# 06_TOFs.net
KiCad netlist of a schematic drawn in Altium Designer
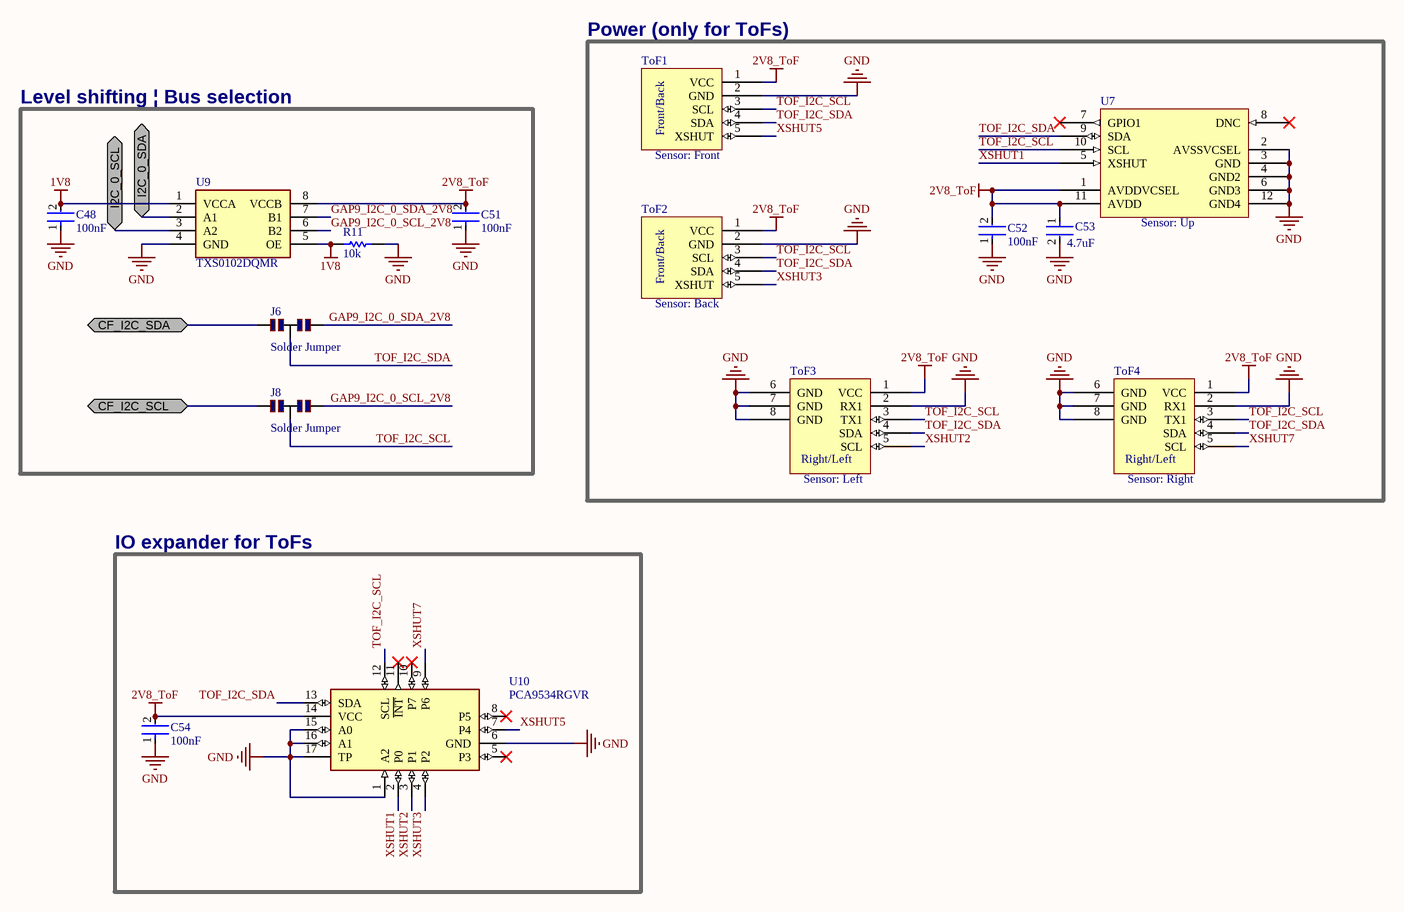
[diagram p0: 06_TOFs.SchDoc]

(export (version "E")
  (design (tool "Eeschema 10.0.6"))
  (components
    (comp (ref "C48")
      (value "100nF")
      (footprint "FP-C1005-050-0_05-MFG")
      (description "Multilayer Ceramic Capacitors 100nF ±10% 25V X5R SMD 0402")
      (fields (field (name "TOLERANCE") "10%") (field (name "VOLTAGE") "25V"))
      (libsource (lib "Altium Content Vault") (part "b4654b650e69147ec39a6b967a45e02"))
    )
    (comp (ref "C51")
      (value "100nF")
      (footprint "FP-C1005-050-0_05-MFG")
      (description "Multilayer Ceramic Capacitors 100nF ±10% 25V X5R SMD 0402")
      (fields (field (name "TOLERANCE") "10%") (field (name "VOLTAGE") "25V"))
      (libsource (lib "Altium Content Vault") (part "b4654b650e69147ec39a6b967a45e02"))
    )
    (comp (ref "C52")
      (value "100nF")
      (footprint "FP-C1005-050-0_05-MFG")
      (description "Multilayer Ceramic Capacitors 100nF ±10% 25V X5R SMD 0402")
      (fields (field (name "TOLERANCE") "10%") (field (name "VOLTAGE") "25V"))
      (libsource (lib "Altium Content Vault") (part "b4654b650e69147ec39a6b967a45e02"))
    )
    (comp (ref "C53")
      (value "4.7uF")
      (footprint "FP-C1005-050-0_15-MFG")
      (description "CAP CER 4.7UF 6.3V X5R 0402")
      (fields (field (name "VOLTAGE") "6.3V") (field (name "TOLERANCE") "10%"))
      (libsource (lib "Altium Content Vault") (part "02cd4be3c70576c341d710602a673aa"))
    )
    (comp (ref "C54")
      (value "100nF")
      (footprint "FP-C1005-050-0_05-MFG")
      (description "Multilayer Ceramic Capacitors 100nF ±10% 25V X5R SMD 0402")
      (fields (field (name "TOLERANCE") "10%") (field (name "VOLTAGE") "25V"))
      (libsource (lib "Altium Content Vault") (part "b4654b650e69147ec39a6b967a45e02"))
    )
    (comp (ref "J6")
      (value "Solder Jumper")
      (footprint "Jumper 3 pins")
      (description "Solder Jumper 3 Pads")
      (libsource (lib "gap9_deck") (part "CMP-00467-5"))
    )
    (comp (ref "J8")
      (value "Solder Jumper")
      (footprint "Jumper 3 pins")
      (description "Solder Jumper 3 Pads")
      (libsource (lib "gap9_deck") (part "CMP-00467-5"))
    )
    (comp (ref "R11")
      (value "10k")
      (footprint "RESC0603X28X15LL05T05")
      (fields (field (name "MANUFACTURER") "Vishay Dale") (field (name "PART NUMBER") "CRCW020110K0FNED"))
      (libsource (lib "Altium Content Vault") (part "RES"))
    )
    (comp (ref "ToF1")
      (value "~")
      (footprint "ToF_Front_Back")
      (description "ToF PCBs (DNM)")
      (libsource (lib "gap9_deck") (part "ToF_Front_Back"))
    )
    (comp (ref "ToF2")
      (value "~")
      (footprint "ToF_Front_Back")
      (description "ToF PCBs (DNM)")
      (libsource (lib "gap9_deck") (part "ToF_Front_Back"))
    )
    (comp (ref "ToF3")
      (value "~")
      (footprint "ToF_Right_Left")
      (libsource (lib "gap9_deck") (part "ToF_Right_Letf"))
    )
    (comp (ref "ToF4")
      (value "~")
      (footprint "ToF_Right_Left")
      (libsource (lib "gap9_deck") (part "ToF_Right_Letf"))
    )
    (comp (ref "U7")
      (value "VL53L1CXV0FY/1")
      (footprint "TOF")
      (fields (field (name "MANUFACTURER") "STMicroelectronics"))
      (libsource (lib "Pulp_Shield_wolf") (part "VL53L1X"))
    )
    (comp (ref "U9")
      (value "TXS0102DQMR")
      (footprint "SON40P120X180X40-8N")
      (description "Integrated Circuit")
      (fields (field (name "MOUSER PART NUMBER") "595-TXS0102DQMR"))
      (libsource (lib "*") (part "TXS0102DQMR"))
    )
    (comp (ref "U10")
      (value "PCA9534RGVR")
      (footprint "SamacSys:QFN65P400X400X100-17N-D")
      (description "Undefined or Miscellaneous")
      (fields (field (name "MOUSER PART NUMBER") "595-PCA9534RGVR"))
      (libsource (lib "*") (part "PCA9534RGVR"))
    )
  )
  (nets
    (net (code "1") (name "/CF_I2C_SCL") (class "Default")
      (node (ref "J8") (pin "1") (pinfunction "1_1") (pintype "passive"))
    )
    (net (code "2") (name "/CF_I2C_SDA") (class "Default")
      (node (ref "J6") (pin "1") (pinfunction "1_1") (pintype "passive"))
    )
    (net (code "3") (name "/GAP9_I2C_0_SCL_2V8") (class "Default")
      (node (ref "J8") (pin "3") (pinfunction "3_3") (pintype "passive"))
      (node (ref "U9") (pin "6") (pinfunction "B2_6") (pintype "passive"))
    )
    (net (code "4") (name "/GAP9_I2C_0_SDA_2V8") (class "Default")
      (node (ref "J6") (pin "3") (pinfunction "3_3") (pintype "passive"))
      (node (ref "U9") (pin "7") (pinfunction "B1_7") (pintype "passive"))
    )
    (net (code "5") (name "/I2C_0_SCL") (class "Default")
      (node (ref "U9") (pin "3") (pinfunction "A2_3") (pintype "passive"))
    )
    (net (code "6") (name "/I2C_0_SDA") (class "Default")
      (node (ref "U9") (pin "2") (pinfunction "A1_2") (pintype "passive"))
    )
    (net (code "7") (name "/TOF_I2C_SCL") (class "Default")
      (node (ref "J8") (pin "2") (pinfunction "2_2") (pintype "passive"))
      (node (ref "ToF1") (pin "3") (pinfunction "SCL_3") (pintype "bidirectional"))
      (node (ref "ToF2") (pin "3") (pinfunction "SCL_3") (pintype "bidirectional"))
      (node (ref "ToF3") (pin "3") (pinfunction "TX1_3") (pintype "bidirectional"))
      (node (ref "ToF4") (pin "3") (pinfunction "TX1_3") (pintype "bidirectional"))
      (node (ref "U10") (pin "12") (pinfunction "SCL_12") (pintype "bidirectional"))
      (node (ref "U7") (pin "10") (pinfunction "SCL_10") (pintype "input"))
    )
    (net (code "8") (name "/TOF_I2C_SDA") (class "Default")
      (node (ref "J6") (pin "2") (pinfunction "2_2") (pintype "passive"))
      (node (ref "ToF1") (pin "4") (pinfunction "SDA_4") (pintype "bidirectional"))
      (node (ref "ToF2") (pin "4") (pinfunction "SDA_4") (pintype "bidirectional"))
      (node (ref "ToF3") (pin "4") (pinfunction "SDA_4") (pintype "bidirectional"))
      (node (ref "ToF4") (pin "4") (pinfunction "SDA_4") (pintype "bidirectional"))
      (node (ref "U10") (pin "13") (pinfunction "SDA_13") (pintype "bidirectional"))
      (node (ref "U7") (pin "9") (pinfunction "SDA_9") (pintype "bidirectional"))
    )
    (net (code "9") (name "/XSHUT1") (class "Default")
      (node (ref "U10") (pin "2") (pinfunction "P0_2") (pintype "bidirectional"))
      (node (ref "U7") (pin "5") (pinfunction "XSHUT_5") (pintype "input"))
    )
    (net (code "10") (name "/XSHUT2") (class "Default")
      (node (ref "ToF3") (pin "5") (pinfunction "SCL_5") (pintype "bidirectional"))
      (node (ref "U10") (pin "3") (pinfunction "P1_3") (pintype "bidirectional"))
    )
    (net (code "11") (name "/XSHUT3") (class "Default")
      (node (ref "ToF2") (pin "5") (pinfunction "XSHUT_5") (pintype "bidirectional"))
      (node (ref "U10") (pin "4") (pinfunction "P2_4") (pintype "bidirectional"))
    )
    (net (code "12") (name "/XSHUT5") (class "Default")
      (node (ref "ToF1") (pin "5") (pinfunction "XSHUT_5") (pintype "bidirectional"))
      (node (ref "U10") (pin "7") (pinfunction "P4_7") (pintype "bidirectional"))
    )
    (net (code "13") (name "/XSHUT7") (class "Default")
      (node (ref "ToF4") (pin "5") (pinfunction "SCL_5") (pintype "bidirectional"))
      (node (ref "U10") (pin "9") (pinfunction "P6_9") (pintype "bidirectional"))
    )
    (net (code "14") (name "1V8") (class "Default")
      (node (ref "C48") (pin "2") (pinfunction "2_2") (pintype "passive"))
      (node (ref "R11") (pin "2") (pinfunction "2_2") (pintype "passive"))
      (node (ref "U9") (pin "1") (pinfunction "VCCA_1") (pintype "passive"))
      (node (ref "U9") (pin "5") (pinfunction "OE_5") (pintype "passive"))
    )
    (net (code "15") (name "2V8_ToF") (class "Default")
      (node (ref "C51") (pin "2") (pinfunction "2_2") (pintype "passive"))
      (node (ref "C52") (pin "2") (pinfunction "2_2") (pintype "passive"))
      (node (ref "C53") (pin "1") (pinfunction "1_1") (pintype "passive"))
      (node (ref "C54") (pin "2") (pinfunction "2_2") (pintype "passive"))
      (node (ref "ToF1") (pin "1") (pinfunction "VCC_1") (pintype "power_in"))
      (node (ref "ToF2") (pin "1") (pinfunction "VCC_1") (pintype "power_in"))
      (node (ref "ToF3") (pin "1") (pinfunction "VCC_1") (pintype "power_in"))
      (node (ref "ToF4") (pin "1") (pinfunction "VCC_1") (pintype "power_in"))
      (node (ref "U10") (pin "14") (pinfunction "VCC_14") (pintype "passive"))
      (node (ref "U7") (pin "1") (pinfunction "AVDDVCSEL_1") (pintype "power_in"))
      (node (ref "U7") (pin "11") (pinfunction "AVDD_11") (pintype "power_in"))
      (node (ref "U9") (pin "8") (pinfunction "VCCB_8") (pintype "passive"))
    )
    (net (code "16") (name "GND") (class "Default")
      (node (ref "C48") (pin "1") (pinfunction "1_1") (pintype "passive"))
      (node (ref "C51") (pin "1") (pinfunction "1_1") (pintype "passive"))
      (node (ref "C52") (pin "1") (pinfunction "1_1") (pintype "passive"))
      (node (ref "C53") (pin "2") (pinfunction "2_2") (pintype "passive"))
      (node (ref "C54") (pin "1") (pinfunction "1_1") (pintype "passive"))
      (node (ref "R11") (pin "1") (pinfunction "1_1") (pintype "passive"))
      (node (ref "ToF1") (pin "2") (pinfunction "GND_2") (pintype "power_in"))
      (node (ref "ToF2") (pin "2") (pinfunction "GND_2") (pintype "power_in"))
      (node (ref "ToF3") (pin "2") (pinfunction "RX1_2") (pintype "power_in"))
      (node (ref "ToF3") (pin "6") (pinfunction "GND_6") (pintype "passive"))
      (node (ref "ToF3") (pin "7") (pinfunction "GND_7") (pintype "passive"))
      (node (ref "ToF3") (pin "8") (pinfunction "GND_8") (pintype "passive"))
      (node (ref "ToF4") (pin "2") (pinfunction "RX1_2") (pintype "power_in"))
      (node (ref "ToF4") (pin "6") (pinfunction "GND_6") (pintype "passive"))
      (node (ref "ToF4") (pin "7") (pinfunction "GND_7") (pintype "passive"))
      (node (ref "ToF4") (pin "8") (pinfunction "GND_8") (pintype "passive"))
      (node (ref "U10") (pin "1") (pinfunction "A2_1") (pintype "input"))
      (node (ref "U10") (pin "15") (pinfunction "A0_15") (pintype "bidirectional"))
      (node (ref "U10") (pin "16") (pinfunction "A1_16") (pintype "bidirectional"))
      (node (ref "U10") (pin "17") (pinfunction "TP_17") (pintype "passive"))
      (node (ref "U10") (pin "6") (pinfunction "GND_6") (pintype "passive"))
      (node (ref "U7") (pin "12") (pinfunction "GND4_12") (pintype "power_in"))
      (node (ref "U7") (pin "2") (pinfunction "AVSSVCSEL_2") (pintype "power_in"))
      (node (ref "U7") (pin "3") (pinfunction "GND_3") (pintype "power_in"))
      (node (ref "U7") (pin "4") (pinfunction "GND2_4") (pintype "power_in"))
      (node (ref "U7") (pin "6") (pinfunction "GND3_6") (pintype "power_in"))
      (node (ref "U9") (pin "4") (pinfunction "GND_4") (pintype "passive"))
    )
    (net (code "17") (name "unconnected-(U7-DNC-Pad8)") (class "Default")
      (node (ref "U7") (pin "8") (pinfunction "DNC_8") (pintype "input+no_connect"))
    )
    (net (code "18") (name "unconnected-(U7-GPIO1-Pad7)") (class "Default")
      (node (ref "U7") (pin "7") (pinfunction "GPIO1_7") (pintype "output+no_connect"))
    )
    (net (code "19") (name "unconnected-(U10-P3-Pad5)") (class "Default")
      (node (ref "U10") (pin "5") (pinfunction "P3_5") (pintype "bidirectional+no_connect"))
    )
    (net (code "20") (name "unconnected-(U10-P5-Pad8)") (class "Default")
      (node (ref "U10") (pin "8") (pinfunction "P5_8") (pintype "bidirectional+no_connect"))
    )
    (net (code "21") (name "unconnected-(U10-P7-Pad10)") (class "Default")
      (node (ref "U10") (pin "10") (pinfunction "P7_10") (pintype "bidirectional+no_connect"))
    )
    (net (code "22") (name "unconnected-(U10-~{INT}-Pad11)") (class "Default")
      (node (ref "U10") (pin "11") (pinfunction "~{INT}_11") (pintype "output+no_connect"))
    )
  )
)
